# mainboard.net
KiCad netlist of a schematic drawn in EAGLE
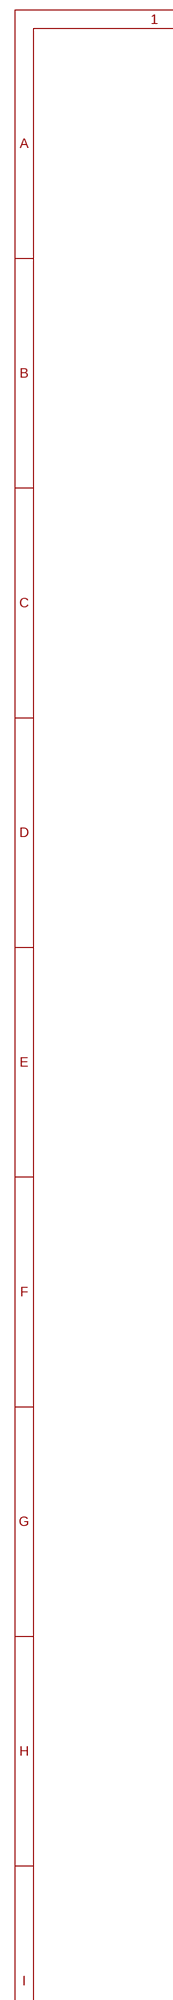
[diagram p0: schematic, sheet 1, part 1 of 2]
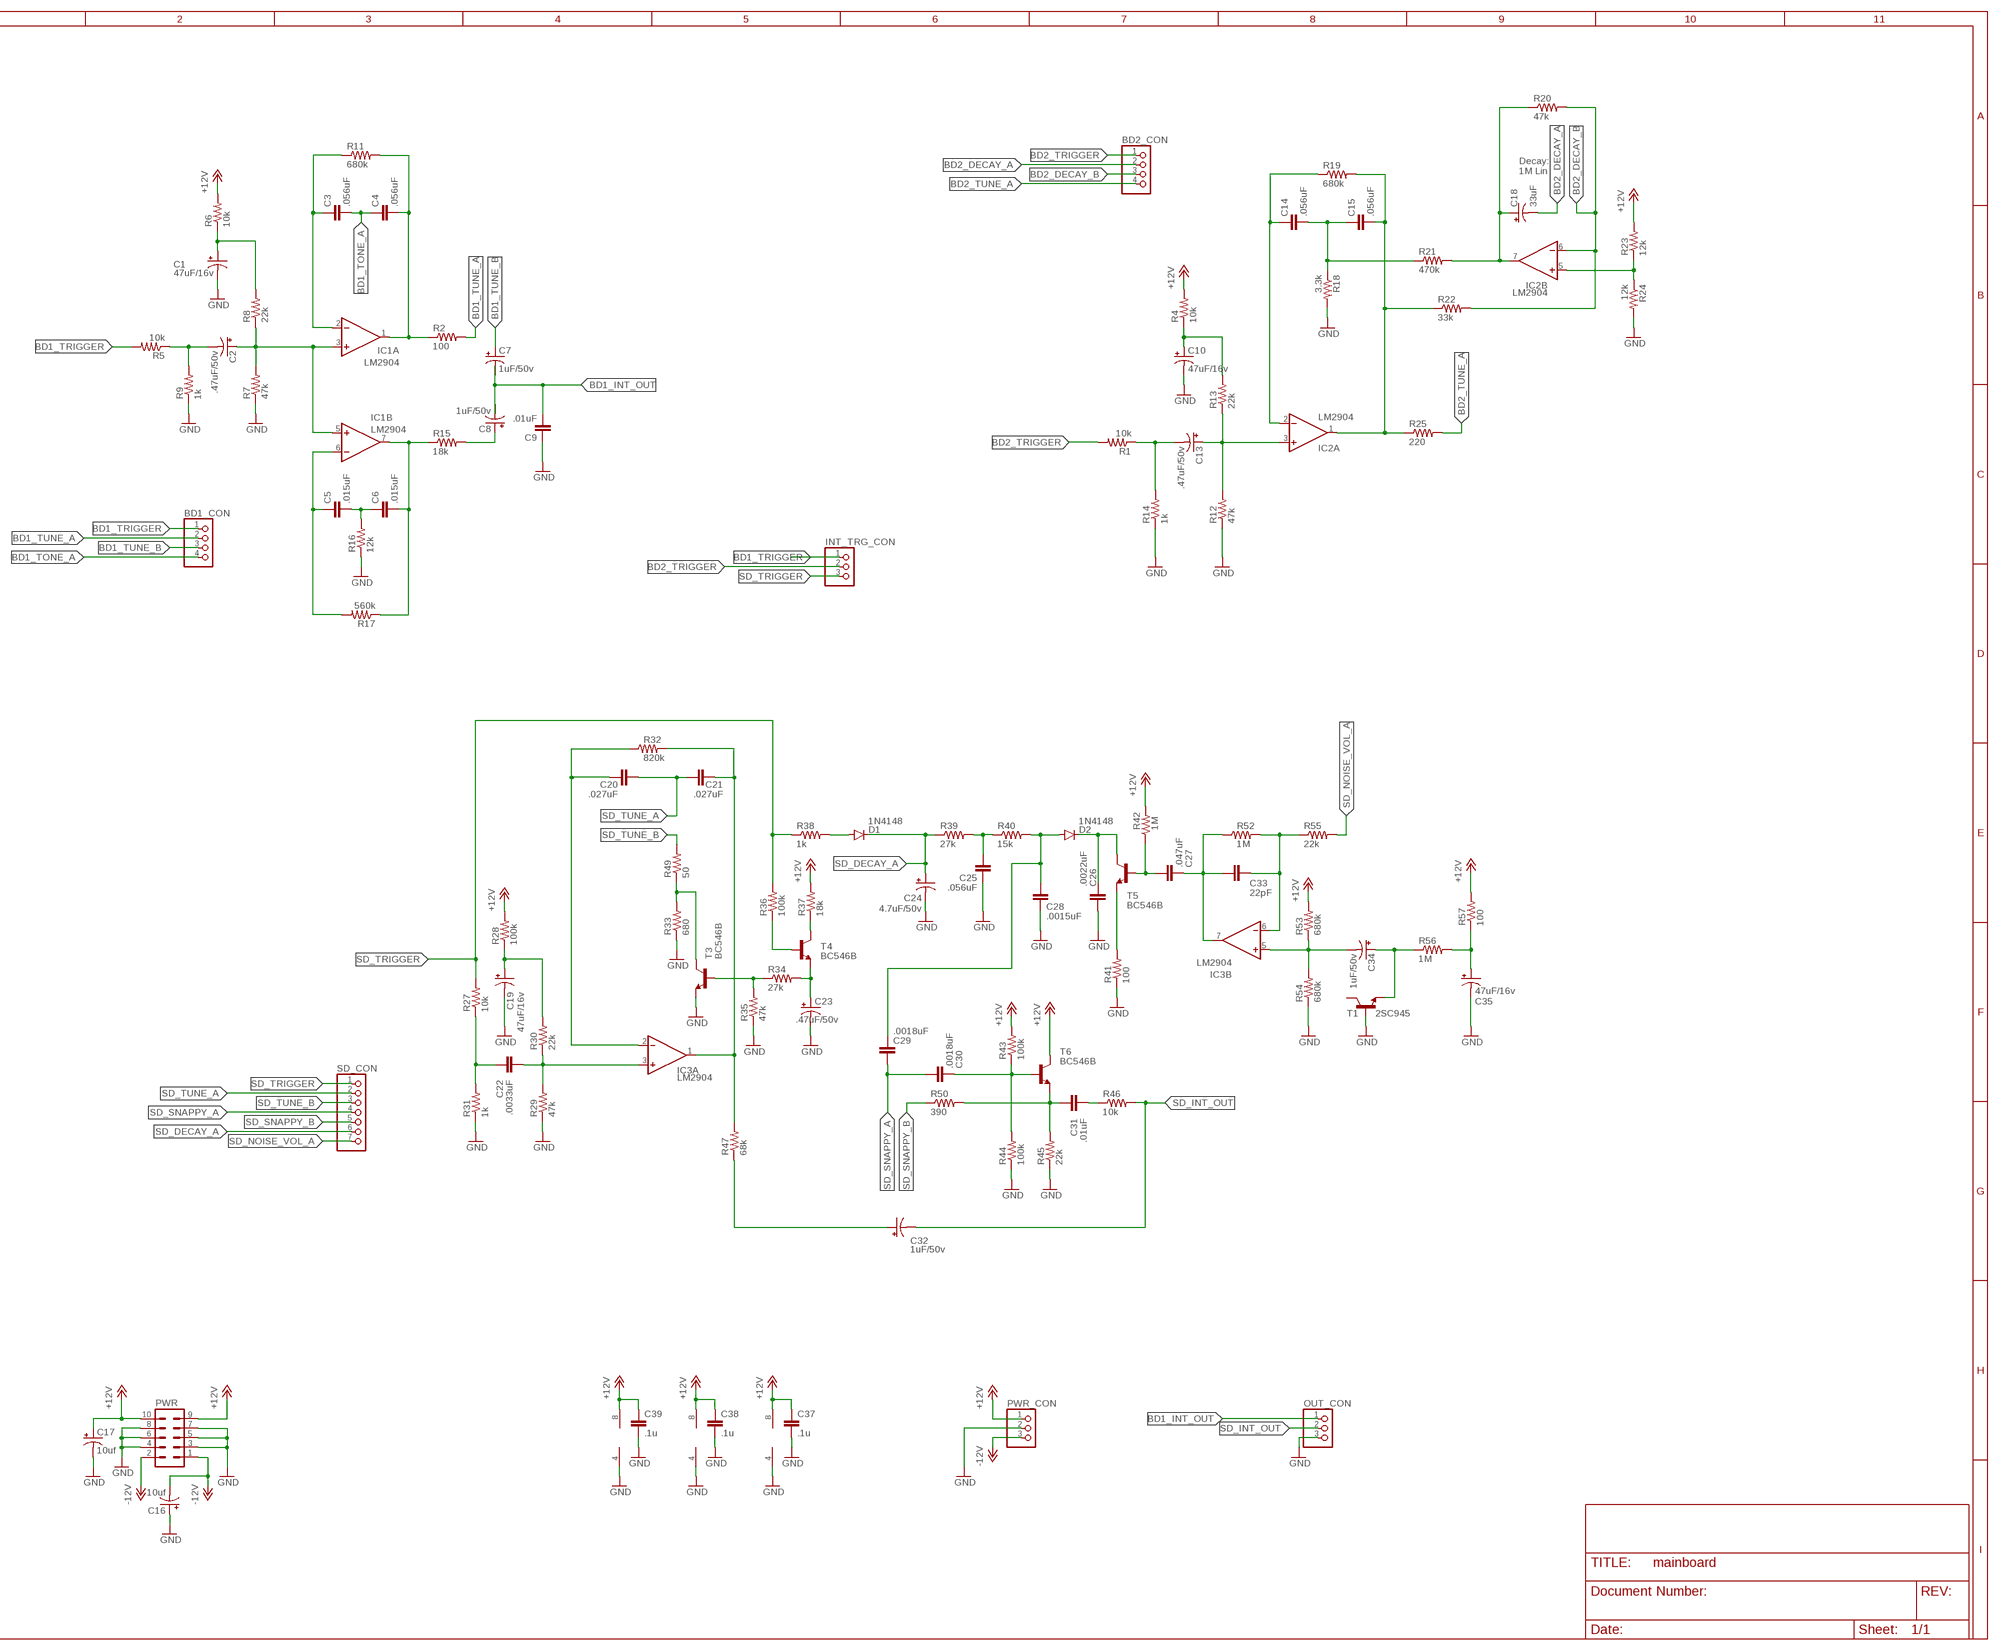
[diagram p1: schematic, sheet 1, part 2 of 2]

(export (version "E")
  (design (tool "Eeschema 10.0.6"))
  (components
    (comp (ref "BD1_CON")
      (value "PINHD-1X4")
      (footprint "eagle-import:1X04")
      (libsource (lib "eagle-import") (part "PINHD-1X4"))
    )
    (comp (ref "BD2_CON")
      (value "PINHD-1X4")
      (footprint "eagle-import:1X04")
      (libsource (lib "eagle-import") (part "PINHD-1X4"))
    )
    (comp (ref "C1")
      (value "47uF/16v")
      (footprint "eagle-import:E2,5-5")
      (libsource (lib "eagle-import") (part "resistor_CPOL-USE2.5-5"))
    )
    (comp (ref "C2")
      (value ".47uF/50v")
      (footprint "eagle-import:E2,5-5")
      (libsource (lib "eagle-import") (part "resistor_CPOL-USE2.5-5"))
    )
    (comp (ref "C3")
      (value ".056uF")
      (footprint "eagle-import:C050-024X044")
      (libsource (lib "eagle-import") (part "C-EU050-024X044"))
    )
    (comp (ref "C4")
      (value ".056uF")
      (footprint "eagle-import:C050-024X044")
      (libsource (lib "eagle-import") (part "C-EU050-024X044"))
    )
    (comp (ref "C5")
      (value ".015uF")
      (footprint "eagle-import:C050-024X044")
      (libsource (lib "eagle-import") (part "C-EU050-024X044"))
    )
    (comp (ref "C6")
      (value ".015uF")
      (footprint "eagle-import:C050-024X044")
      (libsource (lib "eagle-import") (part "C-EU050-024X044"))
    )
    (comp (ref "C7")
      (value "1uF/50v")
      (footprint "eagle-import:E2,5-5")
      (libsource (lib "eagle-import") (part "resistor_CPOL-USE2.5-5"))
    )
    (comp (ref "C8")
      (value "1uF/50v")
      (footprint "eagle-import:E2,5-5")
      (libsource (lib "eagle-import") (part "CPOL-USE2.5-5"))
    )
    (comp (ref "C9")
      (value ".01uF")
      (footprint "eagle-import:C050-024X044")
      (libsource (lib "eagle-import") (part "C-EU050-024X044"))
    )
    (comp (ref "C10")
      (value "47uF/16v")
      (footprint "eagle-import:E2,5-6")
      (libsource (lib "eagle-import") (part "resistor_CPOL-USE2.5-6"))
    )
    (comp (ref "C13")
      (value ".47uF/50v")
      (footprint "eagle-import:E2,5-6")
      (libsource (lib "eagle-import") (part "resistor_CPOL-USE2.5-6"))
    )
    (comp (ref "C14")
      (value ".056uF")
      (footprint "eagle-import:C050-024X044")
      (libsource (lib "eagle-import") (part "C-EU050-024X044"))
    )
    (comp (ref "C15")
      (value ".056uF")
      (footprint "eagle-import:C050-024X044")
      (libsource (lib "eagle-import") (part "C-EU050-024X044"))
    )
    (comp (ref "C16")
      (value "10uf")
      (footprint "eagle-import:E2,5-5")
      (libsource (lib "eagle-import") (part "resistor_CPOL-USE2.5-5"))
    )
    (comp (ref "C17")
      (value "10uf")
      (footprint "eagle-import:E2,5-5")
      (libsource (lib "eagle-import") (part "resistor_CPOL-USE2.5-5"))
    )
    (comp (ref "C18")
      (value "33uF")
      (footprint "eagle-import:E2,5-5")
      (libsource (lib "eagle-import") (part "CPOL-USE2.5-5"))
    )
    (comp (ref "C19")
      (value "47uF/16v")
      (footprint "eagle-import:E2,5-6")
      (libsource (lib "eagle-import") (part "resistor_CPOL-USE2.5-6"))
    )
    (comp (ref "C20")
      (value ".027uF")
      (footprint "eagle-import:C050-024X044")
      (libsource (lib "eagle-import") (part "C-EU050-024X044"))
    )
    (comp (ref "C21")
      (value ".027uF")
      (footprint "eagle-import:C050-024X044")
      (libsource (lib "eagle-import") (part "C-EU050-024X044"))
    )
    (comp (ref "C22")
      (value ".0033uF")
      (footprint "eagle-import:C050-024X044")
      (libsource (lib "eagle-import") (part "C-EU050-024X044"))
    )
    (comp (ref "C23")
      (value ".47uF/50v")
      (footprint "eagle-import:E2,5-6")
      (libsource (lib "eagle-import") (part "resistor_CPOL-USE2.5-6"))
    )
    (comp (ref "C24")
      (value "4.7uF/50v")
      (footprint "eagle-import:E2,5-6")
      (libsource (lib "eagle-import") (part "resistor_CPOL-USE2.5-6"))
    )
    (comp (ref "C25")
      (value ".056uF")
      (footprint "eagle-import:C050-024X044")
      (libsource (lib "eagle-import") (part "C-EU050-024X044"))
    )
    (comp (ref "C26")
      (value ".0022uF")
      (footprint "eagle-import:C050-024X044")
      (libsource (lib "eagle-import") (part "C-EU050-024X044"))
    )
    (comp (ref "C27")
      (value ".047uF")
      (footprint "eagle-import:C050-024X044")
      (libsource (lib "eagle-import") (part "C-EU050-024X044"))
    )
    (comp (ref "C28")
      (value ".0015uF")
      (footprint "eagle-import:C050-024X044")
      (libsource (lib "eagle-import") (part "C-EU050-024X044"))
    )
    (comp (ref "C29")
      (value ".0018uF")
      (footprint "eagle-import:C050-024X044")
      (libsource (lib "eagle-import") (part "C-EU050-024X044"))
    )
    (comp (ref "C30")
      (value ".0018uF")
      (footprint "eagle-import:C050-024X044")
      (libsource (lib "eagle-import") (part "C-EU050-024X044"))
    )
    (comp (ref "C31")
      (value ".01uF")
      (footprint "eagle-import:C050-024X044")
      (libsource (lib "eagle-import") (part "C-EU050-024X044"))
    )
    (comp (ref "C32")
      (value "1uF/50v")
      (footprint "eagle-import:E2,5-6")
      (libsource (lib "eagle-import") (part "resistor_CPOL-USE2.5-6"))
    )
    (comp (ref "C33")
      (value "22pF")
      (footprint "eagle-import:C050-024X044")
      (libsource (lib "eagle-import") (part "C-EU050-024X044"))
    )
    (comp (ref "C34")
      (value "1uF/50v")
      (footprint "eagle-import:E2,5-5")
      (libsource (lib "eagle-import") (part "resistor_CPOL-USE2.5-5"))
    )
    (comp (ref "C35")
      (value "47uF/16v")
      (footprint "eagle-import:E2,5-5")
      (libsource (lib "eagle-import") (part "resistor_CPOL-USE2.5-5"))
    )
    (comp (ref "C37")
      (value ".1u")
      (footprint "eagle-import:C050-024X044")
      (libsource (lib "eagle-import") (part "C-EU050-024X044"))
    )
    (comp (ref "C38")
      (value ".1u")
      (footprint "eagle-import:C050-024X044")
      (libsource (lib "eagle-import") (part "C-EU050-024X044"))
    )
    (comp (ref "C39")
      (value ".1u")
      (footprint "eagle-import:C050-024X044")
      (libsource (lib "eagle-import") (part "C-EU050-024X044"))
    )
    (comp (ref "D1")
      (value "1N4148")
      (footprint "eagle-import:DO35-7")
      (libsource (lib "eagle-import") (part "1N4148DO35-7"))
    )
    (comp (ref "D2")
      (value "1N4148")
      (footprint "eagle-import:DO35-7")
      (libsource (lib "eagle-import") (part "1N4148DO35-7"))
    )
    (comp (ref "IC1")
      (value "LM2904")
      (footprint "eagle-import:DIL08")
      (libsource (lib "eagle-import") (part "TL072P"))
    )
    (comp (ref "IC2")
      (value "LM2904")
      (footprint "eagle-import:DIL08")
      (libsource (lib "eagle-import") (part "TL072P"))
    )
    (comp (ref "IC3")
      (value "LM2904")
      (footprint "eagle-import:DIL08")
      (libsource (lib "eagle-import") (part "TL072P"))
    )
    (comp (ref "INT_TRG_CON")
      (value "PINHD-1X3")
      (footprint "eagle-import:1X03")
      (libsource (lib "eagle-import") (part "PINHD-1X3"))
    )
    (comp (ref "OUT_CON")
      (value "PINHD-1X3")
      (footprint "eagle-import:1X03")
      (libsource (lib "eagle-import") (part "PINHD-1X3"))
    )
    (comp (ref "PWR")
      (value "ML10")
      (footprint "eagle-import:ML10")
      (libsource (lib "eagle-import") (part "ML10"))
    )
    (comp (ref "PWR_CON")
      (value "PINHD-1X3")
      (footprint "eagle-import:1X03")
      (libsource (lib "eagle-import") (part "PINHD-1X3"))
    )
    (comp (ref "R1")
      (value "10k")
      (footprint "eagle-import:0207_7")
      (libsource (lib "eagle-import") (part "R-US_0207/7"))
    )
    (comp (ref "R2")
      (value "100")
      (footprint "eagle-import:0207_7")
      (libsource (lib "eagle-import") (part "R-US_0207/7"))
    )
    (comp (ref "R4")
      (value "10k")
      (footprint "eagle-import:0207_7")
      (libsource (lib "eagle-import") (part "R-US_0207/7"))
    )
    (comp (ref "R5")
      (value "10k")
      (footprint "eagle-import:0207_7")
      (libsource (lib "eagle-import") (part "R-US_0207/7"))
    )
    (comp (ref "R6")
      (value "10k")
      (footprint "eagle-import:0207_7")
      (libsource (lib "eagle-import") (part "R-US_0207/7"))
    )
    (comp (ref "R7")
      (value "47k")
      (footprint "eagle-import:0207_7")
      (libsource (lib "eagle-import") (part "R-US_0207/7"))
    )
    (comp (ref "R8")
      (value "22k")
      (footprint "eagle-import:0207_7")
      (libsource (lib "eagle-import") (part "R-US_0207/7"))
    )
    (comp (ref "R9")
      (value "1k")
      (footprint "eagle-import:0207_7")
      (libsource (lib "eagle-import") (part "R-US_0207/7"))
    )
    (comp (ref "R11")
      (value "680k")
      (footprint "eagle-import:0207_7")
      (libsource (lib "eagle-import") (part "R-US_0207/7"))
    )
    (comp (ref "R12")
      (value "47k")
      (footprint "eagle-import:0207_7")
      (libsource (lib "eagle-import") (part "R-US_0207/7"))
    )
    (comp (ref "R13")
      (value "22k")
      (footprint "eagle-import:0207_7")
      (libsource (lib "eagle-import") (part "R-US_0207/7"))
    )
    (comp (ref "R14")
      (value "1k")
      (footprint "eagle-import:0207_7")
      (libsource (lib "eagle-import") (part "R-US_0207/7"))
    )
    (comp (ref "R15")
      (value "18k")
      (footprint "eagle-import:0207_7")
      (libsource (lib "eagle-import") (part "R-US_0207/7"))
    )
    (comp (ref "R16")
      (value "12k")
      (footprint "eagle-import:0207_7")
      (libsource (lib "eagle-import") (part "R-US_0207/7"))
    )
    (comp (ref "R17")
      (value "560k")
      (footprint "eagle-import:0207_7")
      (libsource (lib "eagle-import") (part "R-US_0207/7"))
    )
    (comp (ref "R18")
      (value "3.3k")
      (footprint "eagle-import:0207_7")
      (libsource (lib "eagle-import") (part "R-US_0207/7"))
    )
    (comp (ref "R19")
      (value "680k")
      (footprint "eagle-import:0207_7")
      (libsource (lib "eagle-import") (part "R-US_0207/7"))
    )
    (comp (ref "R20")
      (value "47k")
      (footprint "eagle-import:0207_7")
      (libsource (lib "eagle-import") (part "R-US_0207/7"))
    )
    (comp (ref "R21")
      (value "470k")
      (footprint "eagle-import:0207_7")
      (libsource (lib "eagle-import") (part "R-US_0207/7"))
    )
    (comp (ref "R22")
      (value "33k")
      (footprint "eagle-import:0207_7")
      (libsource (lib "eagle-import") (part "R-US_0207/7"))
    )
    (comp (ref "R23")
      (value "12k")
      (footprint "eagle-import:0207_7")
      (libsource (lib "eagle-import") (part "R-US_0207/7"))
    )
    (comp (ref "R24")
      (value "12k")
      (footprint "eagle-import:0207_7")
      (libsource (lib "eagle-import") (part "R-US_0207/7"))
    )
    (comp (ref "R25")
      (value "220")
      (footprint "eagle-import:0207_7")
      (libsource (lib "eagle-import") (part "R-US_0207/7"))
    )
    (comp (ref "R27")
      (value "10k")
      (footprint "eagle-import:0207_7")
      (libsource (lib "eagle-import") (part "R-US_0207/7"))
    )
    (comp (ref "R28")
      (value "100k")
      (footprint "eagle-import:0207_7")
      (libsource (lib "eagle-import") (part "R-US_0207/7"))
    )
    (comp (ref "R29")
      (value "47k")
      (footprint "eagle-import:0207_7")
      (libsource (lib "eagle-import") (part "R-US_0207/7"))
    )
    (comp (ref "R30")
      (value "22k")
      (footprint "eagle-import:0207_7")
      (libsource (lib "eagle-import") (part "R-US_0207/7"))
    )
    (comp (ref "R31")
      (value "1k")
      (footprint "eagle-import:0207_7")
      (libsource (lib "eagle-import") (part "R-US_0207/7"))
    )
    (comp (ref "R32")
      (value "820k")
      (footprint "eagle-import:0207_2V")
      (libsource (lib "eagle-import") (part "resistor_R-US_0207/2V"))
    )
    (comp (ref "R33")
      (value "680")
      (footprint "eagle-import:0207_7")
      (libsource (lib "eagle-import") (part "R-US_0207/7"))
    )
    (comp (ref "R34")
      (value "27k")
      (footprint "eagle-import:0207_7")
      (libsource (lib "eagle-import") (part "R-US_0207/7"))
    )
    (comp (ref "R35")
      (value "47k")
      (footprint "eagle-import:0207_7")
      (libsource (lib "eagle-import") (part "R-US_0207/7"))
    )
    (comp (ref "R36")
      (value "100k")
      (footprint "eagle-import:0207_7")
      (libsource (lib "eagle-import") (part "R-US_0207/7"))
    )
    (comp (ref "R37")
      (value "18k")
      (footprint "eagle-import:0207_7")
      (libsource (lib "eagle-import") (part "R-US_0207/7"))
    )
    (comp (ref "R38")
      (value "1k")
      (footprint "eagle-import:0207_7")
      (libsource (lib "eagle-import") (part "R-US_0207/7"))
    )
    (comp (ref "R39")
      (value "27k")
      (footprint "eagle-import:0207_7")
      (libsource (lib "eagle-import") (part "R-US_0207/7"))
    )
    (comp (ref "R40")
      (value "15k")
      (footprint "eagle-import:0207_7")
      (libsource (lib "eagle-import") (part "R-US_0207/7"))
    )
    (comp (ref "R41")
      (value "100")
      (footprint "eagle-import:0207_7")
      (libsource (lib "eagle-import") (part "R-US_0207/7"))
    )
    (comp (ref "R42")
      (value "1M")
      (footprint "eagle-import:0207_7")
      (libsource (lib "eagle-import") (part "R-US_0207/7"))
    )
    (comp (ref "R43")
      (value "100k")
      (footprint "eagle-import:0207_7")
      (libsource (lib "eagle-import") (part "R-US_0207/7"))
    )
    (comp (ref "R44")
      (value "100k")
      (footprint "eagle-import:0207_7")
      (libsource (lib "eagle-import") (part "R-US_0207/7"))
    )
    (comp (ref "R45")
      (value "22k")
      (footprint "eagle-import:0207_7")
      (libsource (lib "eagle-import") (part "R-US_0207/7"))
    )
    (comp (ref "R46")
      (value "10k")
      (footprint "eagle-import:0207_7")
      (libsource (lib "eagle-import") (part "R-US_0207/7"))
    )
    (comp (ref "R47")
      (value "68k")
      (footprint "eagle-import:0207_7")
      (libsource (lib "eagle-import") (part "R-US_0207/7"))
    )
    (comp (ref "R49")
      (value "50")
      (footprint "eagle-import:0207_7")
      (libsource (lib "eagle-import") (part "R-US_0207/7"))
    )
    (comp (ref "R50")
      (value "390")
      (footprint "eagle-import:0207_7")
      (libsource (lib "eagle-import") (part "R-US_0207/7"))
    )
    (comp (ref "R52")
      (value "1M")
      (footprint "eagle-import:0207_7")
      (libsource (lib "eagle-import") (part "R-US_0207/7"))
    )
    (comp (ref "R53")
      (value "680k")
      (footprint "eagle-import:0207_7")
      (libsource (lib "eagle-import") (part "R-US_0207/7"))
    )
    (comp (ref "R54")
      (value "680k")
      (footprint "eagle-import:0207_7")
      (libsource (lib "eagle-import") (part "R-US_0207/7"))
    )
    (comp (ref "R55")
      (value "22k")
      (footprint "eagle-import:0207_7")
      (libsource (lib "eagle-import") (part "R-US_0207/7"))
    )
    (comp (ref "R56")
      (value "1M")
      (footprint "eagle-import:0207_7")
      (libsource (lib "eagle-import") (part "R-US_0207/7"))
    )
    (comp (ref "R57")
      (value "100")
      (footprint "eagle-import:0207_7")
      (libsource (lib "eagle-import") (part "R-US_0207/7"))
    )
    (comp (ref "SD_CON")
      (value "PINHD-1X7")
      (footprint "eagle-import:1X07")
      (libsource (lib "eagle-import") (part "PINHD-1X7"))
    )
    (comp (ref "T1")
      (value "2SC945")
      (footprint "eagle-import:TO92-ECB")
      (libsource (lib "eagle-import") (part "2SC945"))
    )
    (comp (ref "T3")
      (value "BC546B")
      (footprint "eagle-import:TO92-CBE")
      (libsource (lib "eagle-import") (part "-NPN-TO92-CBEBC546"))
    )
    (comp (ref "T4")
      (value "BC546B")
      (footprint "eagle-import:TO92-CBE")
      (libsource (lib "eagle-import") (part "-NPN-TO92-CBEBC546"))
    )
    (comp (ref "T5")
      (value "BC546B")
      (footprint "eagle-import:TO92-CBE")
      (libsource (lib "eagle-import") (part "-NPN-TO92-CBEBC546"))
    )
    (comp (ref "T6")
      (value "BC546B")
      (footprint "eagle-import:TO92-CBE")
      (libsource (lib "eagle-import") (part "-NPN-TO92-CBEBC546"))
    )
  )
  (nets
    (net (code "1") (name "+12V") (class "Default")
      (node (ref "C17") (pin "+") (pinfunction "+_+") (pintype "passive"))
      (node (ref "C37") (pin "1") (pinfunction "1_1") (pintype "passive"))
      (node (ref "C38") (pin "1") (pinfunction "1_1") (pintype "passive"))
      (node (ref "C39") (pin "1") (pinfunction "1_1") (pintype "passive"))
      (node (ref "IC1") (pin "8") (pinfunction "V+_8") (pintype "power_in"))
      (node (ref "IC2") (pin "8") (pinfunction "V+_8") (pintype "power_in"))
      (node (ref "IC3") (pin "8") (pinfunction "V+_8") (pintype "power_in"))
      (node (ref "PWR") (pin "10") (pinfunction "10_10") (pintype "passive"))
      (node (ref "PWR") (pin "9") (pinfunction "9_9") (pintype "passive"))
      (node (ref "PWR_CON") (pin "1") (pinfunction "1_1") (pintype "passive"))
      (node (ref "R23") (pin "2") (pinfunction "2_2") (pintype "passive"))
      (node (ref "R28") (pin "2") (pinfunction "2_2") (pintype "passive"))
      (node (ref "R37") (pin "2") (pinfunction "2_2") (pintype "passive"))
      (node (ref "R4") (pin "2") (pinfunction "2_2") (pintype "passive"))
      (node (ref "R42") (pin "2") (pinfunction "2_2") (pintype "passive"))
      (node (ref "R43") (pin "2") (pinfunction "2_2") (pintype "passive"))
      (node (ref "R53") (pin "2") (pinfunction "2_2") (pintype "passive"))
      (node (ref "R57") (pin "2") (pinfunction "2_2") (pintype "passive"))
      (node (ref "R6") (pin "2") (pinfunction "2_2") (pintype "passive"))
      (node (ref "T6") (pin "C") (pinfunction "C_C") (pintype "passive"))
    )
    (net (code "2") (name "-12V") (class "Default")
      (node (ref "C16") (pin "-") (pinfunction "-_-") (pintype "passive"))
      (node (ref "PWR") (pin "1") (pinfunction "1_1") (pintype "passive"))
      (node (ref "PWR") (pin "2") (pinfunction "2_2") (pintype "passive"))
      (node (ref "PWR_CON") (pin "3") (pinfunction "3_3") (pintype "passive"))
    )
    (net (code "3") (name "BD1_INT_OUT") (class "Default")
      (node (ref "C7") (pin "-") (pinfunction "-_-") (pintype "passive"))
      (node (ref "C8") (pin "-") (pinfunction "-_-") (pintype "passive"))
      (node (ref "C9") (pin "2") (pinfunction "2_2") (pintype "passive"))
      (node (ref "OUT_CON") (pin "1") (pinfunction "1_1") (pintype "passive"))
    )
    (net (code "4") (name "BD1_TONE_A") (class "Default")
      (node (ref "BD1_CON") (pin "4") (pinfunction "4_4") (pintype "passive"))
      (node (ref "C3") (pin "2") (pinfunction "2_2") (pintype "passive"))
      (node (ref "C4") (pin "1") (pinfunction "1_1") (pintype "passive"))
    )
    (net (code "5") (name "BD1_TRIGGER") (class "Default")
      (node (ref "BD1_CON") (pin "1") (pinfunction "1_1") (pintype "passive"))
      (node (ref "INT_TRG_CON") (pin "1") (pinfunction "1_1") (pintype "passive"))
      (node (ref "R5") (pin "2") (pinfunction "2_2") (pintype "passive"))
    )
    (net (code "6") (name "BD1_TUNE_A") (class "Default")
      (node (ref "BD1_CON") (pin "2") (pinfunction "2_2") (pintype "passive"))
      (node (ref "R2") (pin "2") (pinfunction "2_2") (pintype "passive"))
    )
    (net (code "7") (name "BD1_TUNE_B") (class "Default")
      (node (ref "BD1_CON") (pin "3") (pinfunction "3_3") (pintype "passive"))
      (node (ref "C7") (pin "+") (pinfunction "+_+") (pintype "passive"))
    )
    (net (code "8") (name "BD2_DECAY_A") (class "Default")
      (node (ref "BD2_CON") (pin "2") (pinfunction "2_2") (pintype "passive"))
      (node (ref "C18") (pin "-") (pinfunction "-_-") (pintype "passive"))
    )
    (net (code "9") (name "BD2_DECAY_B") (class "Default")
      (node (ref "BD2_CON") (pin "3") (pinfunction "3_3") (pintype "passive"))
      (node (ref "IC2") (pin "6") (pinfunction "-IN_6") (pintype "input"))
      (node (ref "R20") (pin "2") (pinfunction "2_2") (pintype "passive"))
      (node (ref "R22") (pin "2") (pinfunction "2_2") (pintype "passive"))
    )
    (net (code "10") (name "BD2_TRIGGER") (class "Default")
      (node (ref "BD2_CON") (pin "1") (pinfunction "1_1") (pintype "passive"))
      (node (ref "INT_TRG_CON") (pin "2") (pinfunction "2_2") (pintype "passive"))
      (node (ref "R1") (pin "2") (pinfunction "2_2") (pintype "passive"))
    )
    (net (code "11") (name "BD2_TUNE_A") (class "Default")
      (node (ref "BD2_CON") (pin "4") (pinfunction "4_4") (pintype "passive"))
      (node (ref "R25") (pin "2") (pinfunction "2_2") (pintype "passive"))
    )
    (net (code "12") (name "GND") (class "Default")
      (node (ref "C1") (pin "-") (pinfunction "-_-") (pintype "passive"))
      (node (ref "C10") (pin "-") (pinfunction "-_-") (pintype "passive"))
      (node (ref "C16") (pin "+") (pinfunction "+_+") (pintype "passive"))
      (node (ref "C17") (pin "-") (pinfunction "-_-") (pintype "passive"))
      (node (ref "C19") (pin "-") (pinfunction "-_-") (pintype "passive"))
      (node (ref "C23") (pin "-") (pinfunction "-_-") (pintype "passive"))
      (node (ref "C24") (pin "-") (pinfunction "-_-") (pintype "passive"))
      (node (ref "C25") (pin "1") (pinfunction "1_1") (pintype "passive"))
      (node (ref "C26") (pin "1") (pinfunction "1_1") (pintype "passive"))
      (node (ref "C28") (pin "1") (pinfunction "1_1") (pintype "passive"))
      (node (ref "C35") (pin "-") (pinfunction "-_-") (pintype "passive"))
      (node (ref "C37") (pin "2") (pinfunction "2_2") (pintype "passive"))
      (node (ref "C38") (pin "2") (pinfunction "2_2") (pintype "passive"))
      (node (ref "C39") (pin "2") (pinfunction "2_2") (pintype "passive"))
      (node (ref "C9") (pin "1") (pinfunction "1_1") (pintype "passive"))
      (node (ref "IC1") (pin "4") (pinfunction "V-_4") (pintype "power_in"))
      (node (ref "IC2") (pin "4") (pinfunction "V-_4") (pintype "power_in"))
      (node (ref "IC3") (pin "4") (pinfunction "V-_4") (pintype "power_in"))
      (node (ref "OUT_CON") (pin "3") (pinfunction "3_3") (pintype "passive"))
      (node (ref "PWR") (pin "3") (pinfunction "3_3") (pintype "passive"))
      (node (ref "PWR") (pin "4") (pinfunction "4_4") (pintype "passive"))
      (node (ref "PWR") (pin "5") (pinfunction "5_5") (pintype "passive"))
      (node (ref "PWR") (pin "6") (pinfunction "6_6") (pintype "passive"))
      (node (ref "PWR") (pin "7") (pinfunction "7_7") (pintype "passive"))
      (node (ref "PWR") (pin "8") (pinfunction "8_8") (pintype "passive"))
      (node (ref "PWR_CON") (pin "2") (pinfunction "2_2") (pintype "passive"))
      (node (ref "R12") (pin "1") (pinfunction "1_1") (pintype "passive"))
      (node (ref "R14") (pin "1") (pinfunction "1_1") (pintype "passive"))
      (node (ref "R16") (pin "1") (pinfunction "1_1") (pintype "passive"))
      (node (ref "R18") (pin "2") (pinfunction "2_2") (pintype "passive"))
      (node (ref "R24") (pin "2") (pinfunction "2_2") (pintype "passive"))
      (node (ref "R29") (pin "1") (pinfunction "1_1") (pintype "passive"))
      (node (ref "R31") (pin "1") (pinfunction "1_1") (pintype "passive"))
      (node (ref "R33") (pin "1") (pinfunction "1_1") (pintype "passive"))
      (node (ref "R35") (pin "1") (pinfunction "1_1") (pintype "passive"))
      (node (ref "R41") (pin "1") (pinfunction "1_1") (pintype "passive"))
      (node (ref "R44") (pin "1") (pinfunction "1_1") (pintype "passive"))
      (node (ref "R45") (pin "1") (pinfunction "1_1") (pintype "passive"))
      (node (ref "R54") (pin "1") (pinfunction "1_1") (pintype "passive"))
      (node (ref "R7") (pin "1") (pinfunction "1_1") (pintype "passive"))
      (node (ref "R9") (pin "1") (pinfunction "1_1") (pintype "passive"))
      (node (ref "T1") (pin "B") (pinfunction "B_B") (pintype "passive"))
      (node (ref "T3") (pin "E") (pinfunction "E_E") (pintype "passive"))
    )
    (net (code "13") (name "Net-(C1-Pad+)") (class "Default")
      (node (ref "C1") (pin "+") (pinfunction "+_+") (pintype "passive"))
      (node (ref "R6") (pin "1") (pinfunction "1_1") (pintype "passive"))
      (node (ref "R8") (pin "2") (pinfunction "2_2") (pintype "passive"))
    )
    (net (code "14") (name "Net-(C2-Pad-)") (class "Default")
      (node (ref "C2") (pin "-") (pinfunction "-_-") (pintype "passive"))
      (node (ref "R5") (pin "1") (pinfunction "1_1") (pintype "passive"))
      (node (ref "R9") (pin "2") (pinfunction "2_2") (pintype "passive"))
    )
    (net (code "15") (name "Net-(C5-Pad2)") (class "Default")
      (node (ref "C5") (pin "2") (pinfunction "2_2") (pintype "passive"))
      (node (ref "C6") (pin "1") (pinfunction "1_1") (pintype "passive"))
      (node (ref "R16") (pin "2") (pinfunction "2_2") (pintype "passive"))
    )
    (net (code "16") (name "Net-(C8-Pad+)") (class "Default")
      (node (ref "C8") (pin "+") (pinfunction "+_+") (pintype "passive"))
      (node (ref "R15") (pin "2") (pinfunction "2_2") (pintype "passive"))
    )
    (net (code "17") (name "Net-(C10-Pad+)") (class "Default")
      (node (ref "C10") (pin "+") (pinfunction "+_+") (pintype "passive"))
      (node (ref "R13") (pin "2") (pinfunction "2_2") (pintype "passive"))
      (node (ref "R4") (pin "1") (pinfunction "1_1") (pintype "passive"))
    )
    (net (code "18") (name "Net-(C13-Pad-)") (class "Default")
      (node (ref "C13") (pin "-") (pinfunction "-_-") (pintype "passive"))
      (node (ref "R1") (pin "1") (pinfunction "1_1") (pintype "passive"))
      (node (ref "R14") (pin "2") (pinfunction "2_2") (pintype "passive"))
    )
    (net (code "19") (name "Net-(C14-Pad2)") (class "Default")
      (node (ref "C14") (pin "2") (pinfunction "2_2") (pintype "passive"))
      (node (ref "C15") (pin "1") (pinfunction "1_1") (pintype "passive"))
      (node (ref "R18") (pin "1") (pinfunction "1_1") (pintype "passive"))
      (node (ref "R21") (pin "1") (pinfunction "1_1") (pintype "passive"))
    )
    (net (code "20") (name "Net-(C19-Pad+)") (class "Default")
      (node (ref "C19") (pin "+") (pinfunction "+_+") (pintype "passive"))
      (node (ref "R28") (pin "1") (pinfunction "1_1") (pintype "passive"))
      (node (ref "R30") (pin "2") (pinfunction "2_2") (pintype "passive"))
    )
    (net (code "21") (name "Net-(C22-Pad1)") (class "Default")
      (node (ref "C22") (pin "1") (pinfunction "1_1") (pintype "passive"))
      (node (ref "R27") (pin "1") (pinfunction "1_1") (pintype "passive"))
      (node (ref "R31") (pin "2") (pinfunction "2_2") (pintype "passive"))
    )
    (net (code "22") (name "Net-(C23-Pad+)") (class "Default")
      (node (ref "C23") (pin "+") (pinfunction "+_+") (pintype "passive"))
      (node (ref "R34") (pin "2") (pinfunction "2_2") (pintype "passive"))
      (node (ref "T4") (pin "E") (pinfunction "E_E") (pintype "passive"))
    )
    (net (code "23") (name "Net-(C25-Pad2)") (class "Default")
      (node (ref "C25") (pin "2") (pinfunction "2_2") (pintype "passive"))
      (node (ref "R39") (pin "2") (pinfunction "2_2") (pintype "passive"))
      (node (ref "R40") (pin "1") (pinfunction "1_1") (pintype "passive"))
    )
    (net (code "24") (name "Net-(C26-Pad2)") (class "Default")
      (node (ref "C26") (pin "2") (pinfunction "2_2") (pintype "passive"))
      (node (ref "D2") (pin "C") (pinfunction "C_C") (pintype "passive"))
      (node (ref "T5") (pin "C") (pinfunction "C_C") (pintype "passive"))
    )
    (net (code "25") (name "Net-(C27-Pad1)") (class "Default")
      (node (ref "C27") (pin "1") (pinfunction "1_1") (pintype "passive"))
      (node (ref "R42") (pin "1") (pinfunction "1_1") (pintype "passive"))
      (node (ref "T5") (pin "B") (pinfunction "B_B") (pintype "passive"))
    )
    (net (code "26") (name "Net-(C28-Pad2)") (class "Default")
      (node (ref "C28") (pin "2") (pinfunction "2_2") (pintype "passive"))
      (node (ref "C29") (pin "1") (pinfunction "1_1") (pintype "passive"))
      (node (ref "D2") (pin "A") (pinfunction "A_A") (pintype "passive"))
      (node (ref "R40") (pin "2") (pinfunction "2_2") (pintype "passive"))
    )
    (net (code "27") (name "Net-(C30-Pad2)") (class "Default")
      (node (ref "C30") (pin "2") (pinfunction "2_2") (pintype "passive"))
      (node (ref "R43") (pin "1") (pinfunction "1_1") (pintype "passive"))
      (node (ref "R44") (pin "2") (pinfunction "2_2") (pintype "passive"))
      (node (ref "T6") (pin "B") (pinfunction "B_B") (pintype "passive"))
    )
    (net (code "28") (name "Net-(C31-Pad1)") (class "Default")
      (node (ref "C31") (pin "1") (pinfunction "1_1") (pintype "passive"))
      (node (ref "R45") (pin "2") (pinfunction "2_2") (pintype "passive"))
      (node (ref "R50") (pin "2") (pinfunction "2_2") (pintype "passive"))
      (node (ref "T6") (pin "E") (pinfunction "E_E") (pintype "passive"))
    )
    (net (code "29") (name "Net-(C31-Pad2)") (class "Default")
      (node (ref "C31") (pin "2") (pinfunction "2_2") (pintype "passive"))
      (node (ref "R46") (pin "1") (pinfunction "1_1") (pintype "passive"))
    )
    (net (code "30") (name "Net-(C32-Pad+)") (class "Default")
      (node (ref "C32") (pin "+") (pinfunction "+_+") (pintype "passive"))
      (node (ref "R47") (pin "1") (pinfunction "1_1") (pintype "passive"))
    )
    (net (code "31") (name "Net-(C34-Pad+)") (class "Default")
      (node (ref "C34") (pin "+") (pinfunction "+_+") (pintype "passive"))
      (node (ref "R56") (pin "1") (pinfunction "1_1") (pintype "passive"))
      (node (ref "T1") (pin "E") (pinfunction "E_E") (pintype "passive"))
    )
    (net (code "32") (name "Net-(C35-Pad+)") (class "Default")
      (node (ref "C35") (pin "+") (pinfunction "+_+") (pintype "passive"))
      (node (ref "R56") (pin "2") (pinfunction "2_2") (pintype "passive"))
      (node (ref "R57") (pin "1") (pinfunction "1_1") (pintype "passive"))
    )
    (net (code "33") (name "Net-(D1-PadA)") (class "Default")
      (node (ref "D1") (pin "A") (pinfunction "A_A") (pintype "passive"))
      (node (ref "R38") (pin "2") (pinfunction "2_2") (pintype "passive"))
    )
    (net (code "34") (name "Net-(IC1A-+IN)") (class "Default")
      (node (ref "C2") (pin "+") (pinfunction "+_+") (pintype "passive"))
      (node (ref "IC1") (pin "3") (pinfunction "+IN_3") (pintype "input"))
      (node (ref "IC1") (pin "5") (pinfunction "+IN_5") (pintype "input"))
      (node (ref "R7") (pin "2") (pinfunction "2_2") (pintype "passive"))
      (node (ref "R8") (pin "1") (pinfunction "1_1") (pintype "passive"))
    )
    (net (code "35") (name "Net-(IC1A--IN)") (class "Default")
      (node (ref "C3") (pin "1") (pinfunction "1_1") (pintype "passive"))
      (node (ref "IC1") (pin "2") (pinfunction "-IN_2") (pintype "input"))
      (node (ref "R11") (pin "1") (pinfunction "1_1") (pintype "passive"))
    )
    (net (code "36") (name "Net-(IC1A-OUT)") (class "Default")
      (node (ref "C4") (pin "2") (pinfunction "2_2") (pintype "passive"))
      (node (ref "IC1") (pin "1") (pinfunction "OUT_1") (pintype "output"))
      (node (ref "R11") (pin "2") (pinfunction "2_2") (pintype "passive"))
      (node (ref "R2") (pin "1") (pinfunction "1_1") (pintype "passive"))
    )
    (net (code "37") (name "Net-(IC1B--IN)") (class "Default")
      (node (ref "C5") (pin "1") (pinfunction "1_1") (pintype "passive"))
      (node (ref "IC1") (pin "6") (pinfunction "-IN_6") (pintype "input"))
      (node (ref "R17") (pin "2") (pinfunction "2_2") (pintype "passive"))
    )
    (net (code "38") (name "Net-(IC1B-OUT)") (class "Default")
      (node (ref "C6") (pin "2") (pinfunction "2_2") (pintype "passive"))
      (node (ref "IC1") (pin "7") (pinfunction "OUT_7") (pintype "output"))
      (node (ref "R15") (pin "1") (pinfunction "1_1") (pintype "passive"))
      (node (ref "R17") (pin "1") (pinfunction "1_1") (pintype "passive"))
    )
    (net (code "39") (name "Net-(IC2A-+IN)") (class "Default")
      (node (ref "C13") (pin "+") (pinfunction "+_+") (pintype "passive"))
      (node (ref "IC2") (pin "3") (pinfunction "+IN_3") (pintype "input"))
      (node (ref "R12") (pin "2") (pinfunction "2_2") (pintype "passive"))
      (node (ref "R13") (pin "1") (pinfunction "1_1") (pintype "passive"))
    )
    (net (code "40") (name "Net-(IC2A--IN)") (class "Default")
      (node (ref "C14") (pin "1") (pinfunction "1_1") (pintype "passive"))
      (node (ref "IC2") (pin "2") (pinfunction "-IN_2") (pintype "input"))
      (node (ref "R19") (pin "1") (pinfunction "1_1") (pintype "passive"))
    )
    (net (code "41") (name "Net-(IC2A-OUT)") (class "Default")
      (node (ref "C15") (pin "2") (pinfunction "2_2") (pintype "passive"))
      (node (ref "IC2") (pin "1") (pinfunction "OUT_1") (pintype "output"))
      (node (ref "R19") (pin "2") (pinfunction "2_2") (pintype "passive"))
      (node (ref "R22") (pin "1") (pinfunction "1_1") (pintype "passive"))
      (node (ref "R25") (pin "1") (pinfunction "1_1") (pintype "passive"))
    )
    (net (code "42") (name "Net-(IC2B-+IN)") (class "Default")
      (node (ref "IC2") (pin "5") (pinfunction "+IN_5") (pintype "input"))
      (node (ref "R23") (pin "1") (pinfunction "1_1") (pintype "passive"))
      (node (ref "R24") (pin "1") (pinfunction "1_1") (pintype "passive"))
    )
    (net (code "43") (name "Net-(IC2B-OUT)") (class "Default")
      (node (ref "C18") (pin "+") (pinfunction "+_+") (pintype "passive"))
      (node (ref "IC2") (pin "7") (pinfunction "OUT_7") (pintype "output"))
      (node (ref "R20") (pin "1") (pinfunction "1_1") (pintype "passive"))
      (node (ref "R21") (pin "2") (pinfunction "2_2") (pintype "passive"))
    )
    (net (code "44") (name "Net-(IC3A-+IN)") (class "Default")
      (node (ref "C22") (pin "2") (pinfunction "2_2") (pintype "passive"))
      (node (ref "IC3") (pin "3") (pinfunction "+IN_3") (pintype "input"))
      (node (ref "R29") (pin "2") (pinfunction "2_2") (pintype "passive"))
      (node (ref "R30") (pin "1") (pinfunction "1_1") (pintype "passive"))
    )
    (net (code "45") (name "Net-(IC3A--IN)") (class "Default")
      (node (ref "C20") (pin "1") (pinfunction "1_1") (pintype "passive"))
      (node (ref "IC3") (pin "2") (pinfunction "-IN_2") (pintype "input"))
      (node (ref "R32") (pin "1") (pinfunction "1_1") (pintype "passive"))
    )
    (net (code "46") (name "Net-(IC3A-OUT)") (class "Default")
      (node (ref "C21") (pin "2") (pinfunction "2_2") (pintype "passive"))
      (node (ref "IC3") (pin "1") (pinfunction "OUT_1") (pintype "output"))
      (node (ref "R32") (pin "2") (pinfunction "2_2") (pintype "passive"))
      (node (ref "R47") (pin "2") (pinfunction "2_2") (pintype "passive"))
    )
    (net (code "47") (name "Net-(IC3B-+IN)") (class "Default")
      (node (ref "C34") (pin "-") (pinfunction "-_-") (pintype "passive"))
      (node (ref "IC3") (pin "5") (pinfunction "+IN_5") (pintype "input"))
      (node (ref "R53") (pin "1") (pinfunction "1_1") (pintype "passive"))
      (node (ref "R54") (pin "2") (pinfunction "2_2") (pintype "passive"))
    )
    (net (code "48") (name "Net-(IC3B--IN)") (class "Default")
      (node (ref "C33") (pin "2") (pinfunction "2_2") (pintype "passive"))
      (node (ref "IC3") (pin "6") (pinfunction "-IN_6") (pintype "input"))
      (node (ref "R52") (pin "2") (pinfunction "2_2") (pintype "passive"))
      (node (ref "R55") (pin "1") (pinfunction "1_1") (pintype "passive"))
    )
    (net (code "49") (name "Net-(IC3B-OUT)") (class "Default")
      (node (ref "C27") (pin "2") (pinfunction "2_2") (pintype "passive"))
      (node (ref "C33") (pin "1") (pinfunction "1_1") (pintype "passive"))
      (node (ref "IC3") (pin "7") (pinfunction "OUT_7") (pintype "output"))
      (node (ref "R52") (pin "1") (pinfunction "1_1") (pintype "passive"))
    )
    (net (code "50") (name "Net-(R33-Pad2)") (class "Default")
      (node (ref "R33") (pin "2") (pinfunction "2_2") (pintype "passive"))
      (node (ref "R49") (pin "1") (pinfunction "1_1") (pintype "passive"))
      (node (ref "T3") (pin "C") (pinfunction "C_C") (pintype "passive"))
    )
    (net (code "51") (name "Net-(R34-Pad1)") (class "Default")
      (node (ref "R34") (pin "1") (pinfunction "1_1") (pintype "passive"))
      (node (ref "R35") (pin "2") (pinfunction "2_2") (pintype "passive"))
      (node (ref "T3") (pin "B") (pinfunction "B_B") (pintype "passive"))
    )
    (net (code "52") (name "Net-(R36-Pad1)") (class "Default")
      (node (ref "R36") (pin "1") (pinfunction "1_1") (pintype "passive"))
      (node (ref "T4") (pin "B") (pinfunction "B_B") (pintype "passive"))
    )
    (net (code "53") (name "Net-(R37-Pad1)") (class "Default")
      (node (ref "R37") (pin "1") (pinfunction "1_1") (pintype "passive"))
      (node (ref "T4") (pin "C") (pinfunction "C_C") (pintype "passive"))
    )
    (net (code "54") (name "Net-(R41-Pad2)") (class "Default")
      (node (ref "R41") (pin "2") (pinfunction "2_2") (pintype "passive"))
      (node (ref "T5") (pin "E") (pinfunction "E_E") (pintype "passive"))
    )
    (net (code "55") (name "SD_DECAY_A") (class "Default")
      (node (ref "C24") (pin "+") (pinfunction "+_+") (pintype "passive"))
      (node (ref "D1") (pin "C") (pinfunction "C_C") (pintype "passive"))
      (node (ref "R39") (pin "1") (pinfunction "1_1") (pintype "passive"))
      (node (ref "SD_CON") (pin "6") (pinfunction "6_6") (pintype "passive"))
    )
    (net (code "56") (name "SD_INT_OUT") (class "Default")
      (node (ref "C32") (pin "-") (pinfunction "-_-") (pintype "passive"))
      (node (ref "OUT_CON") (pin "2") (pinfunction "2_2") (pintype "passive"))
      (node (ref "R46") (pin "2") (pinfunction "2_2") (pintype "passive"))
    )
    (net (code "57") (name "SD_NOISE_VOL_A") (class "Default")
      (node (ref "R55") (pin "2") (pinfunction "2_2") (pintype "passive"))
      (node (ref "SD_CON") (pin "7") (pinfunction "7_7") (pintype "passive"))
    )
    (net (code "58") (name "SD_SNAPPY_A") (class "Default")
      (node (ref "C29") (pin "2") (pinfunction "2_2") (pintype "passive"))
      (node (ref "C30") (pin "1") (pinfunction "1_1") (pintype "passive"))
      (node (ref "SD_CON") (pin "4") (pinfunction "4_4") (pintype "passive"))
    )
    (net (code "59") (name "SD_SNAPPY_B") (class "Default")
      (node (ref "R50") (pin "1") (pinfunction "1_1") (pintype "passive"))
      (node (ref "SD_CON") (pin "5") (pinfunction "5_5") (pintype "passive"))
    )
    (net (code "60") (name "SD_TRIGGER") (class "Default")
      (node (ref "INT_TRG_CON") (pin "3") (pinfunction "3_3") (pintype "passive"))
      (node (ref "R27") (pin "2") (pinfunction "2_2") (pintype "passive"))
      (node (ref "R36") (pin "2") (pinfunction "2_2") (pintype "passive"))
      (node (ref "R38") (pin "1") (pinfunction "1_1") (pintype "passive"))
      (node (ref "SD_CON") (pin "1") (pinfunction "1_1") (pintype "passive"))
    )
    (net (code "61") (name "SD_TUNE_A") (class "Default")
      (node (ref "C20") (pin "2") (pinfunction "2_2") (pintype "passive"))
      (node (ref "C21") (pin "1") (pinfunction "1_1") (pintype "passive"))
      (node (ref "SD_CON") (pin "2") (pinfunction "2_2") (pintype "passive"))
    )
    (net (code "62") (name "SD_TUNE_B") (class "Default")
      (node (ref "R49") (pin "2") (pinfunction "2_2") (pintype "passive"))
      (node (ref "SD_CON") (pin "3") (pinfunction "3_3") (pintype "passive"))
    )
    (net (code "63") (name "unconnected-(T1-PadC)") (class "Default")
      (node (ref "T1") (pin "C") (pinfunction "C_C") (pintype "passive"))
    )
  )
)
